# Air_humidity_sensor_v1_9.net
KiCad netlist of a schematic drawn in EAGLE
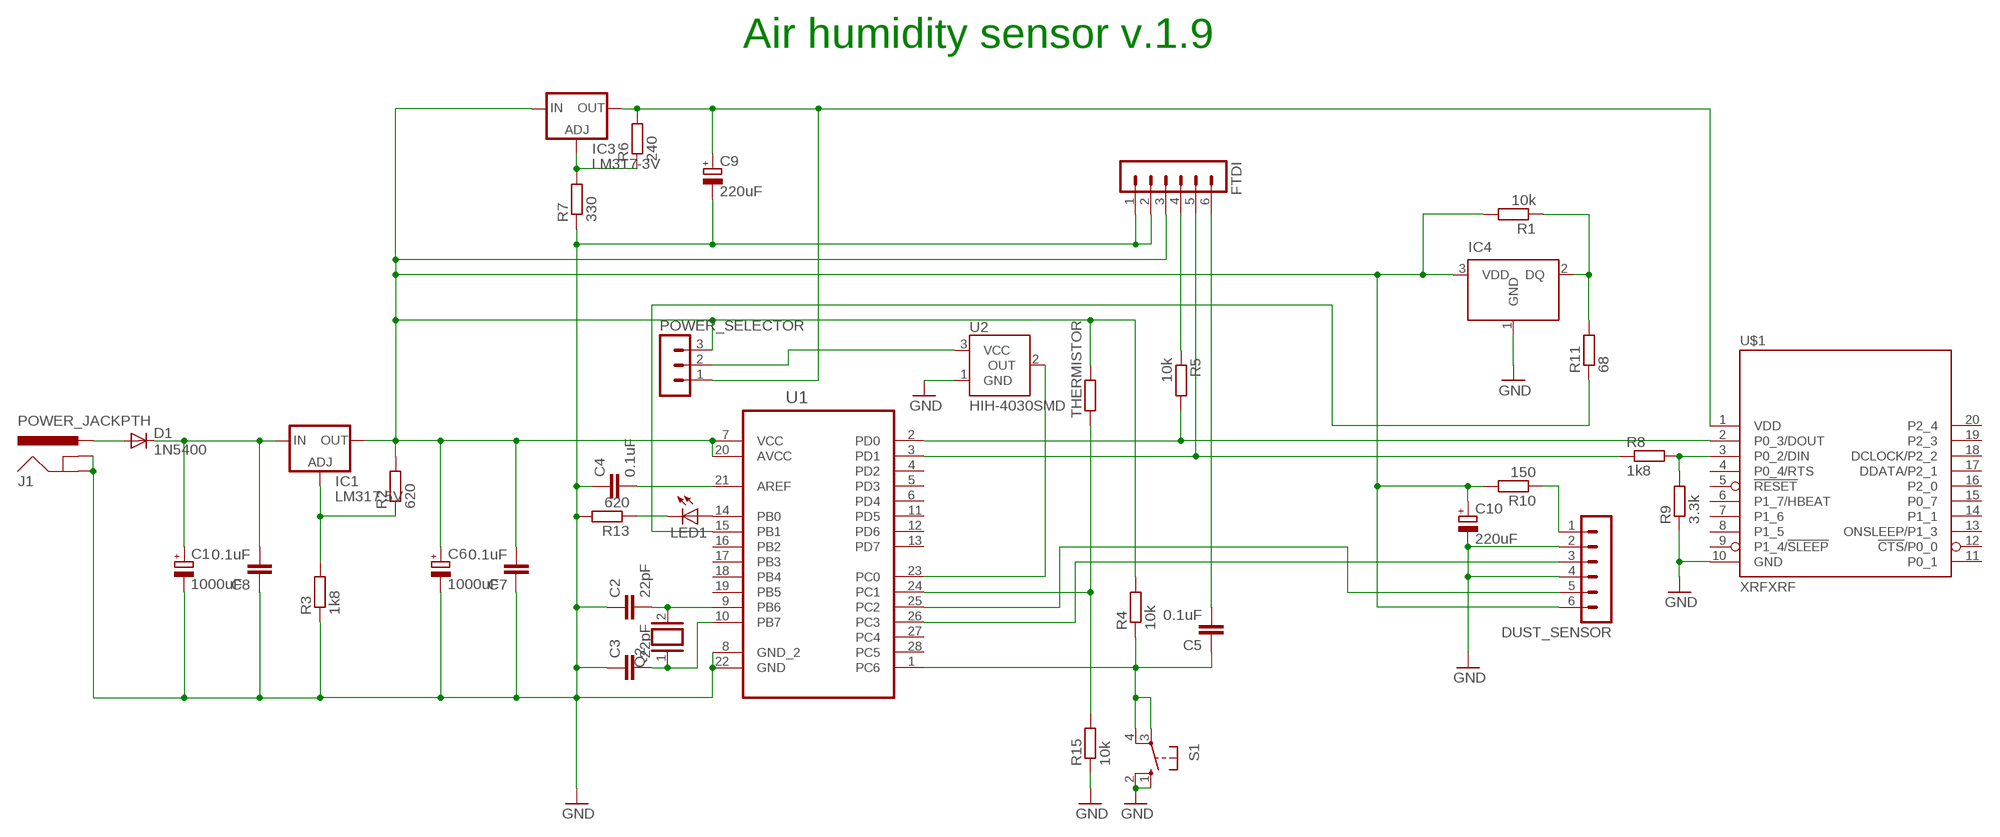
[diagram p0: schematic, sheet 1]

(export (version "E")
  (design (tool "Eeschema 10.0.6"))
  (components
    (comp (ref "C1")
      (value "1000uF")
      (footprint "eagle-import:E5-10,5")
      (libsource (lib "eagle-import") (part "CPOL-EUE5-10.5"))
    )
    (comp (ref "C2")
      (value "22pF")
      (footprint "eagle-import:C025-025X050")
      (libsource (lib "eagle-import") (part "C-EU025-025X050"))
    )
    (comp (ref "C3")
      (value "22pF")
      (footprint "eagle-import:C025-025X050")
      (libsource (lib "eagle-import") (part "C-EU025-025X050"))
    )
    (comp (ref "C4")
      (value "0.1uF")
      (footprint "eagle-import:C075-032X103")
      (libsource (lib "eagle-import") (part "C-EU075-032X103"))
    )
    (comp (ref "C5")
      (value "0.1uF")
      (footprint "eagle-import:C050-025X075")
      (libsource (lib "eagle-import") (part "C-EU050-025X075"))
    )
    (comp (ref "C6")
      (value "1000uF")
      (footprint "eagle-import:E5-10,5")
      (libsource (lib "eagle-import") (part "CPOL-EUE5-10.5"))
    )
    (comp (ref "C7")
      (value "0.1uF")
      (footprint "eagle-import:C050-025X075")
      (libsource (lib "eagle-import") (part "C-EU050-025X075"))
    )
    (comp (ref "C8")
      (value "0.1uF")
      (footprint "eagle-import:C050-025X075")
      (libsource (lib "eagle-import") (part "C-EU050-025X075"))
    )
    (comp (ref "C9")
      (value "220uF")
      (footprint "eagle-import:E3,5-8")
      (libsource (lib "eagle-import") (part "CPOL-EUE3.5-8"))
    )
    (comp (ref "C10")
      (value "220uF")
      (footprint "eagle-import:E5-10,5")
      (libsource (lib "eagle-import") (part "CPOL-EUE5-10.5"))
    )
    (comp (ref "D1")
      (value "1N5400")
      (footprint "eagle-import:DO201-15")
      (libsource (lib "eagle-import") (part "1N5400"))
    )
    (comp (ref "DUST_SENSOR")
      (value "MA06-1")
      (footprint "eagle-import:MA06-1")
      (libsource (lib "eagle-import") (part "MA06-1"))
    )
    (comp (ref "FTDI")
      (value "MA06-1")
      (footprint "eagle-import:MA06-1")
      (libsource (lib "eagle-import") (part "MA06-1"))
    )
    (comp (ref "IC1")
      (value "LM317 5V")
      (footprint "eagle-import:317TS")
      (libsource (lib "eagle-import") (part "LM317TS"))
    )
    (comp (ref "IC3")
      (value "LM317-3V")
      (footprint "eagle-import:317TS")
      (libsource (lib "eagle-import") (part "LM317TS"))
    )
    (comp (ref "IC4")
      (value "DS1820")
      (footprint "eagle-import:TO-92")
      (libsource (lib "eagle-import") (part "DS1820"))
    )
    (comp (ref "J1")
      (value "POWER_JACKPTH")
      (footprint "eagle-import:POWER_JACK_PTH")
      (libsource (lib "eagle-import") (part "POWER_JACKPTH"))
    )
    (comp (ref "LED1")
      (value "LED3MM")
      (footprint "eagle-import:LED3MM")
      (libsource (lib "eagle-import") (part "LED3MM"))
    )
    (comp (ref "POWER_SELECTOR")
      (value "MA03-1")
      (footprint "eagle-import:MA03-1")
      (libsource (lib "eagle-import") (part "MA03-1"))
    )
    (comp (ref "Q2")
      (value "XTAL/S")
      (footprint "eagle-import:QS")
      (libsource (lib "eagle-import") (part "XTAL/S"))
    )
    (comp (ref "R1")
      (value "10k")
      (footprint "eagle-import:0207_5V")
      (libsource (lib "eagle-import") (part "R-EU_0207/5V"))
    )
    (comp (ref "R2")
      (value "620")
      (footprint "eagle-import:0207_5V")
      (libsource (lib "eagle-import") (part "R-EU_0207/5V"))
    )
    (comp (ref "R3")
      (value "1k8")
      (footprint "eagle-import:0207_5V")
      (libsource (lib "eagle-import") (part "R-EU_0207/5V"))
    )
    (comp (ref "R4")
      (value "10k")
      (footprint "eagle-import:0207_5V")
      (libsource (lib "eagle-import") (part "R-EU_0207/5V"))
    )
    (comp (ref "R5")
      (value "10k")
      (footprint "eagle-import:0207_5V")
      (libsource (lib "eagle-import") (part "R-EU_0207/5V"))
    )
    (comp (ref "R6")
      (value "240")
      (footprint "eagle-import:0207_5V")
      (libsource (lib "eagle-import") (part "R-EU_0207/5V"))
    )
    (comp (ref "R7")
      (value "330")
      (footprint "eagle-import:0207_5V")
      (libsource (lib "eagle-import") (part "R-EU_0207/5V"))
    )
    (comp (ref "R8")
      (value "1k8")
      (footprint "eagle-import:0207_12")
      (libsource (lib "eagle-import") (part "R-EU_0207/12"))
    )
    (comp (ref "R9")
      (value "3.3k")
      (footprint "eagle-import:0207_12")
      (libsource (lib "eagle-import") (part "R-EU_0207/12"))
    )
    (comp (ref "R10")
      (value "150")
      (footprint "eagle-import:0207_5V")
      (libsource (lib "eagle-import") (part "R-EU_0207/5V"))
    )
    (comp (ref "R11")
      (value "68")
      (footprint "eagle-import:0207_12")
      (libsource (lib "eagle-import") (part "R-EU_0207/12"))
    )
    (comp (ref "R13")
      (value "620")
      (footprint "eagle-import:0207_12")
      (libsource (lib "eagle-import") (part "R-EU_0207/12"))
    )
    (comp (ref "R15")
      (value "10k")
      (footprint "eagle-import:0207_5V")
      (libsource (lib "eagle-import") (part "R-EU_0207/5V"))
    )
    (comp (ref "S1")
      (value "10-XX")
      (footprint "eagle-import:B3F-10XX")
      (fields (field (name "MPN") "B3F-1000"))
      (libsource (lib "eagle-import") (part "10-XX"))
    )
    (comp (ref "THERMISTOR")
      (value "R-EU_0207/5V")
      (footprint "eagle-import:0207_5V")
      (libsource (lib "eagle-import") (part "R-EU_0207/5V"))
    )
    (comp (ref "U$1")
      (value "XRFXRF")
      (footprint "eagle-import:XRF")
      (libsource (lib "eagle-import") (part "XRFXRF"))
    )
    (comp (ref "U1")
      (value "ATMEGA328P-PU")
      (footprint "eagle-import:DIP254P762X457-28")
      (libsource (lib "eagle-import") (part "ATMEGA328P-PU"))
    )
    (comp (ref "U2")
      (value "HIH-4030SMD")
      (footprint "eagle-import:HIH-4030")
      (libsource (lib "eagle-import") (part "HIH-4030SMD"))
    )
  )
  (nets
    (net (code "1") (name "GND") (class "Default")
      (node (ref "C1") (pin "-") (pinfunction "-_-") (pintype "passive"))
      (node (ref "C10") (pin "-") (pinfunction "-_-") (pintype "passive"))
      (node (ref "C2") (pin "1") (pinfunction "1_1") (pintype "passive"))
      (node (ref "C3") (pin "1") (pinfunction "1_1") (pintype "passive"))
      (node (ref "C4") (pin "1") (pinfunction "1_1") (pintype "passive"))
      (node (ref "C6") (pin "-") (pinfunction "-_-") (pintype "passive"))
      (node (ref "C7") (pin "1") (pinfunction "1_1") (pintype "passive"))
      (node (ref "C8") (pin "1") (pinfunction "1_1") (pintype "passive"))
      (node (ref "C9") (pin "-") (pinfunction "-_-") (pintype "passive"))
      (node (ref "DUST_SENSOR") (pin "2") (pinfunction "2_2") (pintype "passive"))
      (node (ref "DUST_SENSOR") (pin "4") (pinfunction "4_4") (pintype "passive"))
      (node (ref "FTDI") (pin "1") (pinfunction "1_1") (pintype "passive"))
      (node (ref "FTDI") (pin "2") (pinfunction "2_2") (pintype "passive"))
      (node (ref "IC4") (pin "1") (pinfunction "GND_1") (pintype "power_in"))
      (node (ref "J1") (pin "GND") (pinfunction "GND_GND") (pintype "bidirectional"))
      (node (ref "J1") (pin "GNDBREAK") (pinfunction "GNDBREAK_GNDBREAK") (pintype "bidirectional"))
      (node (ref "R13") (pin "2") (pinfunction "2_2") (pintype "passive"))
      (node (ref "R15") (pin "1") (pinfunction "1_1") (pintype "passive"))
      (node (ref "R3") (pin "1") (pinfunction "1_1") (pintype "passive"))
      (node (ref "R7") (pin "1") (pinfunction "1_1") (pintype "passive"))
      (node (ref "R9") (pin "1") (pinfunction "1_1") (pintype "passive"))
      (node (ref "S1") (pin "1") (pinfunction "S_1") (pintype "passive"))
      (node (ref "S1") (pin "2") (pinfunction "S1_2") (pintype "passive"))
      (node (ref "U$1") (pin "10") (pinfunction "GND_10") (pintype "power_in"))
      (node (ref "U1") (pin "22") (pinfunction "GND_22") (pintype "passive"))
      (node (ref "U1") (pin "8") (pinfunction "GND_2_8") (pintype "passive"))
      (node (ref "U2") (pin "1") (pinfunction "GND_1") (pintype "bidirectional"))
    )
    (net (code "2") (name "Net-(C5-Pad2)") (class "Default")
      (node (ref "C5") (pin "2") (pinfunction "2_2") (pintype "passive"))
      (node (ref "FTDI") (pin "6") (pinfunction "6_6") (pintype "passive"))
    )
    (net (code "3") (name "Net-(D1-PadA)") (class "Default")
      (node (ref "D1") (pin "A") (pinfunction "A_A") (pintype "passive"))
      (node (ref "J1") (pin "PWR") (pinfunction "PWR_PWR") (pintype "bidirectional"))
    )
    (net (code "4") (name "Net-(DUST_SENSOR-Pad1)") (class "Default")
      (node (ref "DUST_SENSOR") (pin "1") (pinfunction "1_1") (pintype "passive"))
      (node (ref "R10") (pin "1") (pinfunction "1_1") (pintype "passive"))
    )
    (net (code "5") (name "Net-(FTDI-Pad4)") (class "Default")
      (node (ref "FTDI") (pin "4") (pinfunction "4_4") (pintype "passive"))
      (node (ref "R5") (pin "1") (pinfunction "1_1") (pintype "passive"))
    )
    (net (code "6") (name "Net-(IC1-ADJ)") (class "Default")
      (node (ref "IC1") (pin "1") (pinfunction "ADJ_1") (pintype "input"))
      (node (ref "R2") (pin "1") (pinfunction "1_1") (pintype "passive"))
      (node (ref "R3") (pin "2") (pinfunction "2_2") (pintype "passive"))
    )
    (net (code "7") (name "Net-(IC1-IN)") (class "Default")
      (node (ref "C1") (pin "+") (pinfunction "+_+") (pintype "passive"))
      (node (ref "C8") (pin "2") (pinfunction "2_2") (pintype "passive"))
      (node (ref "D1") (pin "C") (pinfunction "C_C") (pintype "passive"))
      (node (ref "IC1") (pin "3") (pinfunction "IN_3") (pintype "input"))
    )
    (net (code "8") (name "Net-(IC1-OUT)") (class "Default")
      (node (ref "C10") (pin "+") (pinfunction "+_+") (pintype "passive"))
      (node (ref "C6") (pin "+") (pinfunction "+_+") (pintype "passive"))
      (node (ref "C7") (pin "2") (pinfunction "2_2") (pintype "passive"))
      (node (ref "DUST_SENSOR") (pin "6") (pinfunction "6_6") (pintype "passive"))
      (node (ref "FTDI") (pin "3") (pinfunction "3_3") (pintype "passive"))
      (node (ref "IC1") (pin "2") (pinfunction "OUT_2") (pintype "passive"))
      (node (ref "IC3") (pin "3") (pinfunction "IN_3") (pintype "input"))
      (node (ref "IC4") (pin "3") (pinfunction "VDD_3") (pintype "input"))
      (node (ref "POWER_SELECTOR") (pin "3") (pinfunction "3_3") (pintype "passive"))
      (node (ref "R1") (pin "2") (pinfunction "2_2") (pintype "passive"))
      (node (ref "R10") (pin "2") (pinfunction "2_2") (pintype "passive"))
      (node (ref "R2") (pin "2") (pinfunction "2_2") (pintype "passive"))
      (node (ref "R4") (pin "2") (pinfunction "2_2") (pintype "passive"))
      (node (ref "THERMISTOR") (pin "2") (pinfunction "2_2") (pintype "passive"))
      (node (ref "U1") (pin "20") (pinfunction "AVCC_20") (pintype "power_in"))
      (node (ref "U1") (pin "7") (pinfunction "VCC_7") (pintype "power_in"))
    )
    (net (code "9") (name "Net-(IC3-ADJ)") (class "Default")
      (node (ref "IC3") (pin "1") (pinfunction "ADJ_1") (pintype "input"))
      (node (ref "R6") (pin "1") (pinfunction "1_1") (pintype "passive"))
      (node (ref "R7") (pin "2") (pinfunction "2_2") (pintype "passive"))
    )
    (net (code "10") (name "Net-(IC3-OUT)") (class "Default")
      (node (ref "C9") (pin "+") (pinfunction "+_+") (pintype "passive"))
      (node (ref "IC3") (pin "2") (pinfunction "OUT_2") (pintype "passive"))
      (node (ref "POWER_SELECTOR") (pin "1") (pinfunction "1_1") (pintype "passive"))
      (node (ref "R6") (pin "2") (pinfunction "2_2") (pintype "passive"))
      (node (ref "U$1") (pin "1") (pinfunction "VDD_1") (pintype "power_in"))
    )
    (net (code "11") (name "Net-(IC4-DQ)") (class "Default")
      (node (ref "IC4") (pin "2") (pinfunction "DQ_2") (pintype "output"))
      (node (ref "R1") (pin "1") (pinfunction "1_1") (pintype "passive"))
      (node (ref "R11") (pin "2") (pinfunction "2_2") (pintype "passive"))
    )
    (net (code "12") (name "Net-(LED1-C)") (class "Default")
      (node (ref "LED1") (pin "K") (pinfunction "C_K") (pintype "passive"))
      (node (ref "R13") (pin "1") (pinfunction "1_1") (pintype "passive"))
    )
    (net (code "13") (name "Net-(S1-P)") (class "Default")
      (node (ref "C5") (pin "1") (pinfunction "1_1") (pintype "passive"))
      (node (ref "R4") (pin "1") (pinfunction "1_1") (pintype "passive"))
      (node (ref "S1") (pin "3") (pinfunction "P_3") (pintype "passive"))
      (node (ref "S1") (pin "4") (pinfunction "P1_4") (pintype "passive"))
      (node (ref "U1") (pin "1") (pinfunction "PC6_1") (pintype "bidirectional"))
    )
    (net (code "14") (name "Net-(U$1-P0_2{slash}DIN)") (class "Default")
      (node (ref "R8") (pin "2") (pinfunction "2_2") (pintype "passive"))
      (node (ref "R9") (pin "2") (pinfunction "2_2") (pintype "passive"))
      (node (ref "U$1") (pin "3") (pinfunction "P0_2/DIN_3") (pintype "input"))
    )
    (net (code "15") (name "Net-(U$1-P0_3{slash}DOUT)") (class "Default")
      (node (ref "R5") (pin "2") (pinfunction "2_2") (pintype "passive"))
      (node (ref "U$1") (pin "2") (pinfunction "P0_3/DOUT_2") (pintype "output"))
      (node (ref "U1") (pin "2") (pinfunction "PD0_2") (pintype "bidirectional"))
    )
    (net (code "16") (name "Net-(U1-AREF)") (class "Default")
      (node (ref "C4") (pin "2") (pinfunction "2_2") (pintype "passive"))
      (node (ref "U1") (pin "21") (pinfunction "AREF_21") (pintype "input"))
    )
    (net (code "17") (name "Net-(U1-PB0)") (class "Default")
      (node (ref "LED1") (pin "A") (pinfunction "A_A") (pintype "passive"))
      (node (ref "U1") (pin "14") (pinfunction "PB0_14") (pintype "bidirectional"))
    )
    (net (code "18") (name "Net-(U1-PB1)") (class "Default")
      (node (ref "R11") (pin "1") (pinfunction "1_1") (pintype "passive"))
      (node (ref "U1") (pin "15") (pinfunction "PB1_15") (pintype "bidirectional"))
    )
    (net (code "19") (name "Net-(U1-PB6)") (class "Default")
      (node (ref "C2") (pin "2") (pinfunction "2_2") (pintype "passive"))
      (node (ref "Q2") (pin "2") (pinfunction "2_2") (pintype "passive"))
      (node (ref "U1") (pin "9") (pinfunction "PB6_9") (pintype "bidirectional"))
    )
    (net (code "20") (name "Net-(U1-PB7)") (class "Default")
      (node (ref "C3") (pin "2") (pinfunction "2_2") (pintype "passive"))
      (node (ref "Q2") (pin "1") (pinfunction "1_1") (pintype "passive"))
      (node (ref "U1") (pin "10") (pinfunction "PB7_10") (pintype "bidirectional"))
    )
    (net (code "21") (name "Net-(U1-PC0)") (class "Default")
      (node (ref "U1") (pin "23") (pinfunction "PC0_23") (pintype "bidirectional"))
      (node (ref "U2") (pin "2") (pinfunction "OUT_2") (pintype "bidirectional"))
    )
    (net (code "22") (name "Net-(U1-PC1)") (class "Default")
      (node (ref "R15") (pin "2") (pinfunction "2_2") (pintype "passive"))
      (node (ref "THERMISTOR") (pin "1") (pinfunction "1_1") (pintype "passive"))
      (node (ref "U1") (pin "24") (pinfunction "PC1_24") (pintype "bidirectional"))
    )
    (net (code "23") (name "Net-(U1-PC2)") (class "Default")
      (node (ref "DUST_SENSOR") (pin "5") (pinfunction "5_5") (pintype "passive"))
      (node (ref "U1") (pin "25") (pinfunction "PC2_25") (pintype "bidirectional"))
    )
    (net (code "24") (name "Net-(U1-PC3)") (class "Default")
      (node (ref "DUST_SENSOR") (pin "3") (pinfunction "3_3") (pintype "passive"))
      (node (ref "U1") (pin "26") (pinfunction "PC3_26") (pintype "bidirectional"))
    )
    (net (code "25") (name "Net-(U1-PD1)") (class "Default")
      (node (ref "FTDI") (pin "5") (pinfunction "5_5") (pintype "passive"))
      (node (ref "R8") (pin "1") (pinfunction "1_1") (pintype "passive"))
      (node (ref "U1") (pin "3") (pinfunction "PD1_3") (pintype "bidirectional"))
    )
    (net (code "26") (name "Net-(U2-VCC)") (class "Default")
      (node (ref "POWER_SELECTOR") (pin "2") (pinfunction "2_2") (pintype "passive"))
      (node (ref "U2") (pin "3") (pinfunction "VCC_3") (pintype "bidirectional"))
    )
    (net (code "27") (name "unconnected-(U$1-DCLOCK{slash}P2_2-Pad18)") (class "Default")
      (node (ref "U$1") (pin "18") (pinfunction "DCLOCK/P2_2_18") (pintype "bidirectional"))
    )
    (net (code "28") (name "unconnected-(U$1-DDATA{slash}P2_1-Pad17)") (class "Default")
      (node (ref "U$1") (pin "17") (pinfunction "DDATA/P2_1_17") (pintype "bidirectional"))
    )
    (net (code "29") (name "unconnected-(U$1-ONSLEEP{slash}P1_3-Pad13)") (class "Default")
      (node (ref "U$1") (pin "13") (pinfunction "ONSLEEP/P1_3_13") (pintype "bidirectional"))
    )
    (net (code "30") (name "unconnected-(U$1-P0_1-Pad11)") (class "Default")
      (node (ref "U$1") (pin "11") (pinfunction "P0_1_11") (pintype "bidirectional"))
    )
    (net (code "31") (name "unconnected-(U$1-P0_4{slash}RTS-Pad4)") (class "Default")
      (node (ref "U$1") (pin "4") (pinfunction "P0_4/RTS_4") (pintype "bidirectional"))
    )
    (net (code "32") (name "unconnected-(U$1-P0_7-Pad15)") (class "Default")
      (node (ref "U$1") (pin "15") (pinfunction "P0_7_15") (pintype "bidirectional"))
    )
    (net (code "33") (name "unconnected-(U$1-P1_1-Pad14)") (class "Default")
      (node (ref "U$1") (pin "14") (pinfunction "P1_1_14") (pintype "bidirectional"))
    )
    (net (code "34") (name "unconnected-(U$1-P1_4{slash}~{SLEEP}-Pad9)") (class "Default")
      (node (ref "U$1") (pin "9") (pinfunction "P1_4/~{SLEEP}_9") (pintype "bidirectional"))
    )
    (net (code "35") (name "unconnected-(U$1-P1_5-Pad8)") (class "Default")
      (node (ref "U$1") (pin "8") (pinfunction "P1_5_8") (pintype "bidirectional"))
    )
    (net (code "36") (name "unconnected-(U$1-P1_6-Pad7)") (class "Default")
      (node (ref "U$1") (pin "7") (pinfunction "P1_6_7") (pintype "bidirectional"))
    )
    (net (code "37") (name "unconnected-(U$1-P1_7{slash}HBEAT-Pad6)") (class "Default")
      (node (ref "U$1") (pin "6") (pinfunction "P1_7/HBEAT_6") (pintype "bidirectional"))
    )
    (net (code "38") (name "unconnected-(U$1-P2_0-Pad16)") (class "Default")
      (node (ref "U$1") (pin "16") (pinfunction "P2_0_16") (pintype "input"))
    )
    (net (code "39") (name "unconnected-(U$1-P2_3-Pad19)") (class "Default")
      (node (ref "U$1") (pin "19") (pinfunction "P2_3_19") (pintype "bidirectional"))
    )
    (net (code "40") (name "unconnected-(U$1-P2_4-Pad20)") (class "Default")
      (node (ref "U$1") (pin "20") (pinfunction "P2_4_20") (pintype "bidirectional"))
    )
    (net (code "41") (name "unconnected-(U$1-~{CTS}{slash}P0_0-Pad12)") (class "Default")
      (node (ref "U$1") (pin "12") (pinfunction "~{CTS}/P0_0_12") (pintype "output"))
    )
    (net (code "42") (name "unconnected-(U$1-~{RESET}-Pad5)") (class "Default")
      (node (ref "U$1") (pin "5") (pinfunction "~{RESET}_5") (pintype "input"))
    )
    (net (code "43") (name "unconnected-(U1-PB2-Pad16)") (class "Default")
      (node (ref "U1") (pin "16") (pinfunction "PB2_16") (pintype "bidirectional"))
    )
    (net (code "44") (name "unconnected-(U1-PB3-Pad17)") (class "Default")
      (node (ref "U1") (pin "17") (pinfunction "PB3_17") (pintype "bidirectional"))
    )
    (net (code "45") (name "unconnected-(U1-PB4-Pad18)") (class "Default")
      (node (ref "U1") (pin "18") (pinfunction "PB4_18") (pintype "bidirectional"))
    )
    (net (code "46") (name "unconnected-(U1-PB5-Pad19)") (class "Default")
      (node (ref "U1") (pin "19") (pinfunction "PB5_19") (pintype "bidirectional"))
    )
    (net (code "47") (name "unconnected-(U1-PC4-Pad27)") (class "Default")
      (node (ref "U1") (pin "27") (pinfunction "PC4_27") (pintype "bidirectional"))
    )
    (net (code "48") (name "unconnected-(U1-PC5-Pad28)") (class "Default")
      (node (ref "U1") (pin "28") (pinfunction "PC5_28") (pintype "bidirectional"))
    )
    (net (code "49") (name "unconnected-(U1-PD2-Pad4)") (class "Default")
      (node (ref "U1") (pin "4") (pinfunction "PD2_4") (pintype "bidirectional"))
    )
    (net (code "50") (name "unconnected-(U1-PD3-Pad5)") (class "Default")
      (node (ref "U1") (pin "5") (pinfunction "PD3_5") (pintype "bidirectional"))
    )
    (net (code "51") (name "unconnected-(U1-PD4-Pad6)") (class "Default")
      (node (ref "U1") (pin "6") (pinfunction "PD4_6") (pintype "bidirectional"))
    )
    (net (code "52") (name "unconnected-(U1-PD5-Pad11)") (class "Default")
      (node (ref "U1") (pin "11") (pinfunction "PD5_11") (pintype "bidirectional"))
    )
    (net (code "53") (name "unconnected-(U1-PD6-Pad12)") (class "Default")
      (node (ref "U1") (pin "12") (pinfunction "PD6_12") (pintype "bidirectional"))
    )
    (net (code "54") (name "unconnected-(U1-PD7-Pad13)") (class "Default")
      (node (ref "U1") (pin "13") (pinfunction "PD7_13") (pintype "bidirectional"))
    )
  )
)
